# MCU.net
KiCad netlist of a schematic drawn in Altium Designer
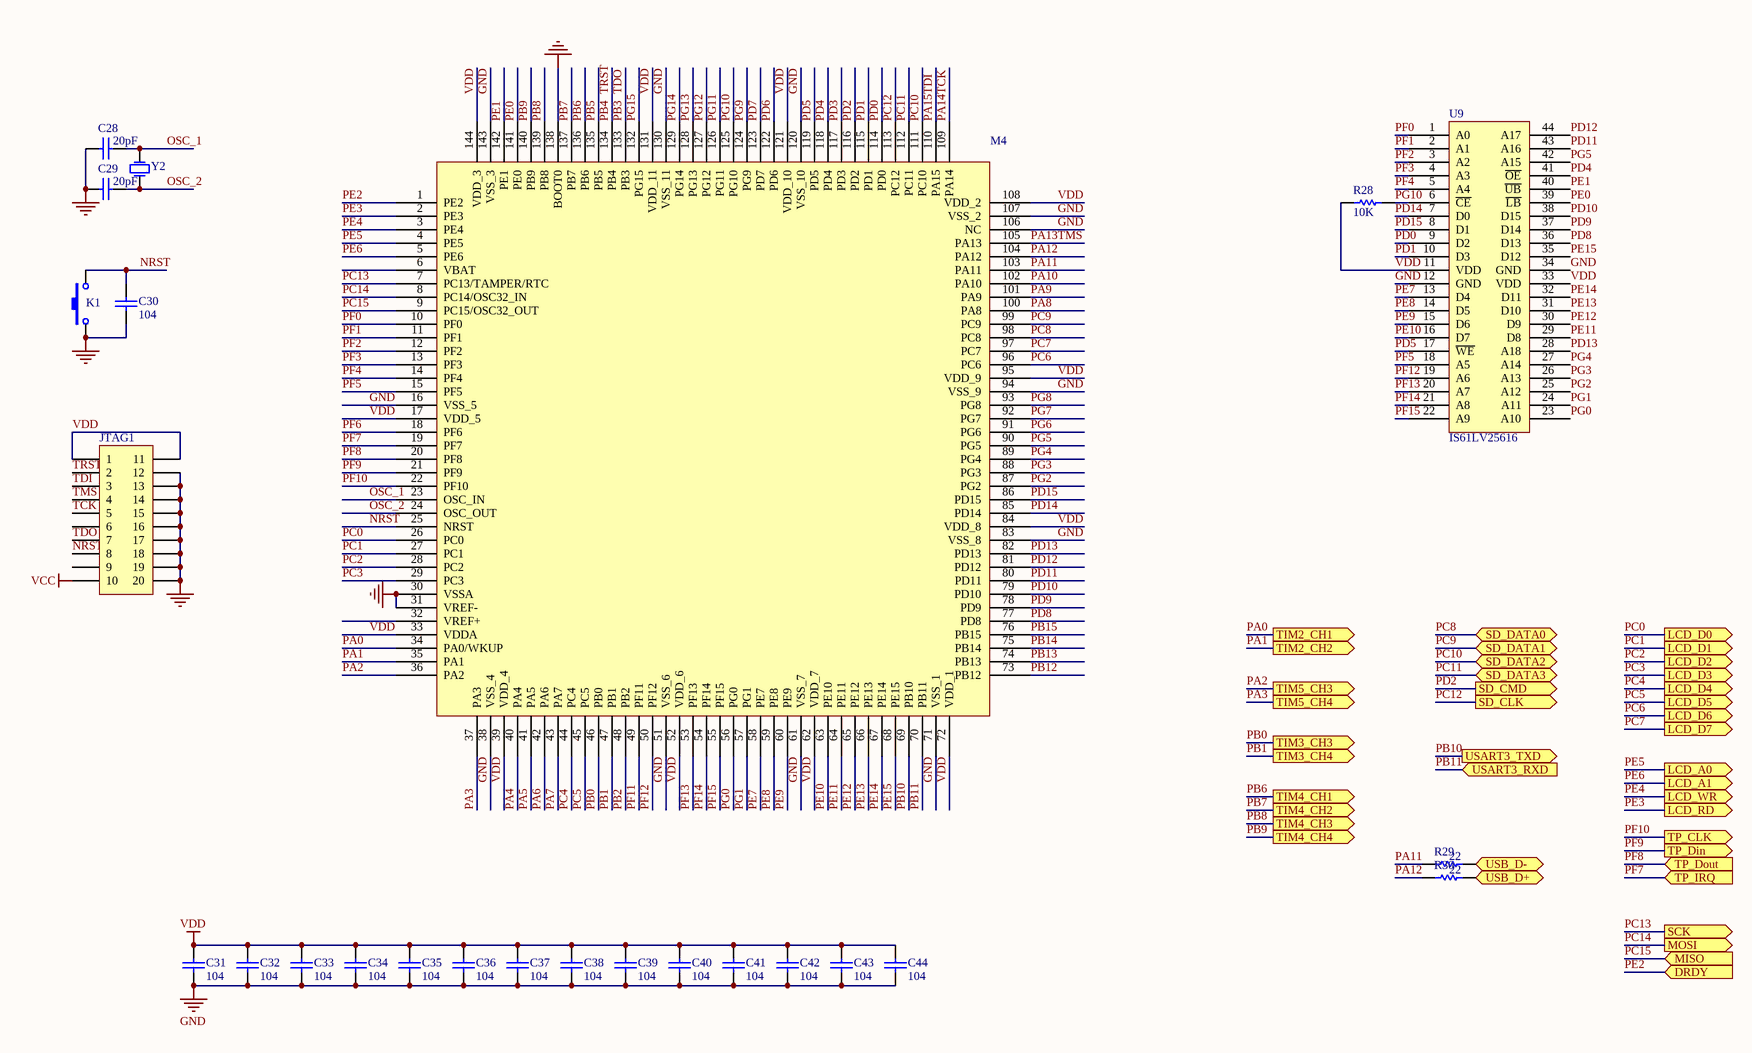
[diagram p0: MCU.SchDoc]

(export (version "E")
  (design (tool "Eeschema 10.0.6"))
  (components
    (comp (ref "C28")
      (value "20pF")
      (footprint "CR2012-0805")
      (description "Capacitor")
      (fields (field (name "Comment") "Cap") (field (name "PUBLISHER") "Altium Limited"))
      (libsource (lib "ComDev") (part "Cap"))
    )
    (comp (ref "C29")
      (value "20pF")
      (footprint "CR2012-0805")
      (description "Capacitor")
      (fields (field (name "Comment") "Cap") (field (name "PUBLISHER") "Altium Limited"))
      (libsource (lib "ComDev") (part "Cap"))
    )
    (comp (ref "C30")
      (value "104")
      (footprint "CR2012-0805")
      (description "Capacitor")
      (fields (field (name "Comment") "Cap") (field (name "PUBLISHER") "Altium Limited"))
      (libsource (lib "ComDev") (part "Cap"))
    )
    (comp (ref "C31")
      (value "104")
      (footprint "CR2012-0805")
      (description "Capacitor")
      (fields (field (name "Comment") "Cap") (field (name "PUBLISHER") "Altium Limited"))
      (libsource (lib "ComDev") (part "Cap"))
    )
    (comp (ref "C32")
      (value "104")
      (footprint "CR2012-0805")
      (description "Capacitor")
      (fields (field (name "Comment") "Cap") (field (name "PUBLISHER") "Altium Limited"))
      (libsource (lib "ComDev") (part "Cap"))
    )
    (comp (ref "C33")
      (value "104")
      (footprint "CR2012-0805")
      (description "Capacitor")
      (fields (field (name "Comment") "Cap") (field (name "PUBLISHER") "Altium Limited"))
      (libsource (lib "ComDev") (part "Cap"))
    )
    (comp (ref "C34")
      (value "104")
      (footprint "CR2012-0805")
      (description "Capacitor")
      (fields (field (name "Comment") "Cap") (field (name "PUBLISHER") "Altium Limited"))
      (libsource (lib "ComDev") (part "Cap"))
    )
    (comp (ref "C35")
      (value "104")
      (footprint "CR2012-0805")
      (description "Capacitor")
      (fields (field (name "Comment") "Cap") (field (name "PUBLISHER") "Altium Limited"))
      (libsource (lib "ComDev") (part "Cap"))
    )
    (comp (ref "C36")
      (value "104")
      (footprint "CR2012-0805")
      (description "Capacitor")
      (fields (field (name "Comment") "Cap") (field (name "PUBLISHER") "Altium Limited"))
      (libsource (lib "ComDev") (part "Cap"))
    )
    (comp (ref "C37")
      (value "104")
      (footprint "CR2012-0805")
      (description "Capacitor")
      (fields (field (name "Comment") "Cap") (field (name "PUBLISHER") "Altium Limited"))
      (libsource (lib "ComDev") (part "Cap"))
    )
    (comp (ref "C38")
      (value "104")
      (footprint "CR2012-0805")
      (description "Capacitor")
      (fields (field (name "Comment") "Cap") (field (name "PUBLISHER") "Altium Limited"))
      (libsource (lib "ComDev") (part "Cap"))
    )
    (comp (ref "C39")
      (value "104")
      (footprint "CR2012-0805")
      (description "Capacitor")
      (fields (field (name "Comment") "Cap") (field (name "PUBLISHER") "Altium Limited"))
      (libsource (lib "ComDev") (part "Cap"))
    )
    (comp (ref "C40")
      (value "104")
      (footprint "CR2012-0805")
      (description "Capacitor")
      (fields (field (name "Comment") "Cap") (field (name "PUBLISHER") "Altium Limited"))
      (libsource (lib "ComDev") (part "Cap"))
    )
    (comp (ref "C41")
      (value "104")
      (footprint "CR2012-0805")
      (description "Capacitor")
      (fields (field (name "Comment") "Cap") (field (name "PUBLISHER") "Altium Limited"))
      (libsource (lib "ComDev") (part "Cap"))
    )
    (comp (ref "C42")
      (value "104")
      (footprint "CR2012-0805")
      (description "Capacitor")
      (fields (field (name "Comment") "Cap") (field (name "PUBLISHER") "Altium Limited"))
      (libsource (lib "ComDev") (part "Cap"))
    )
    (comp (ref "C43")
      (value "104")
      (footprint "CR2012-0805")
      (description "Capacitor")
      (fields (field (name "Comment") "Cap") (field (name "PUBLISHER") "Altium Limited"))
      (libsource (lib "ComDev") (part "Cap"))
    )
    (comp (ref "C44")
      (value "104")
      (footprint "CR2012-0805")
      (description "Capacitor")
      (fields (field (name "Comment") "Cap") (field (name "PUBLISHER") "Altium Limited"))
      (libsource (lib "ComDev") (part "Cap"))
    )
    (comp (ref "JTAG1")
      (value "~")
      (footprint "HDR2X10_CEN")
      (description "Header, 10-Pin, Dual row")
      (fields (field (name "PUBLISHER") "Altium Limited"))
      (libsource (lib "Miscellaneous Connectors") (part "Header 10X2A"))
    )
    (comp (ref "K1")
      (value "SW-PB")
      (footprint "SW-PB-6.5x4.5")
      (description "Switch")
      (fields (field (name "PUBLISHER") "Altium Limited"))
      (libsource (lib "ComDev") (part "SW-PB"))
    )
    (comp (ref "M4")
      (value "STM32")
      (footprint "F-QFP20x20-G144/N")
      (libsource (lib "MCU") (part "STM32_104"))
    )
    (comp (ref "R28")
      (value "10K")
      (footprint "CR2012-0805")
      (description "Resistor")
      (fields (field (name "Comment") "Res") (field (name "PUBLISHER") "Altium Limited"))
      (libsource (lib "ComDev") (part "Res"))
    )
    (comp (ref "R29")
      (value "22")
      (footprint "CR2012-0805")
      (description "Resistor")
      (fields (field (name "Comment") "Res") (field (name "PUBLISHER") "Altium Limited"))
      (libsource (lib "ComDev") (part "Res"))
    )
    (comp (ref "R30")
      (value "22")
      (footprint "CR2012-0805")
      (description "Resistor")
      (fields (field (name "Comment") "Res") (field (name "PUBLISHER") "Altium Limited"))
      (libsource (lib "ComDev") (part "Res"))
    )
    (comp (ref "U9")
      (value "IS61LV25616")
      (footprint "SO-G44/P.8")
      (description "64K*16 SRAM")
      (libsource (lib "MCU") (part "IS61LV25616"))
    )
    (comp (ref "Y2")
      (value "XTAL")
      (footprint "XTAL")
      (description "Crystal Oscillator")
      (fields (field (name "PUBLISHER") "Altium Limited"))
      (libsource (lib "ComDev") (part "XTAL"))
    )
  )
  (nets
    (net (code "1") (name "/NRST") (class "Default")
      (node (ref "C30") (pin "2") (pinfunction "2_2") (pintype "passive"))
      (node (ref "JTAG1") (pin "8") (pinfunction "8_8") (pintype "passive"))
      (node (ref "K1") (pin "2") (pinfunction "2_2") (pintype "passive"))
      (node (ref "M4") (pin "25") (pinfunction "NRST_25") (pintype "passive"))
    )
    (net (code "2") (name "/OSC_1") (class "Default")
      (node (ref "C28") (pin "2") (pinfunction "2_2") (pintype "passive"))
      (node (ref "M4") (pin "23") (pinfunction "OSC_IN_23") (pintype "passive"))
      (node (ref "Y2") (pin "2") (pinfunction "OSC2_2") (pintype "passive"))
    )
    (net (code "3") (name "/OSC_2") (class "Default")
      (node (ref "C29") (pin "2") (pinfunction "2_2") (pintype "passive"))
      (node (ref "M4") (pin "24") (pinfunction "OSC_OUT_24") (pintype "passive"))
      (node (ref "Y2") (pin "1") (pinfunction "OSC1_1") (pintype "passive"))
    )
    (net (code "4") (name "/PA0") (class "Default")
      (node (ref "M4") (pin "34") (pinfunction "PA0/WKUP_34") (pintype "passive"))
    )
    (net (code "5") (name "/PA1") (class "Default")
      (node (ref "M4") (pin "35") (pinfunction "PA1_35") (pintype "passive"))
    )
    (net (code "6") (name "/PA2") (class "Default")
      (node (ref "M4") (pin "36") (pinfunction "PA2_36") (pintype "passive"))
    )
    (net (code "7") (name "/PA3") (class "Default")
      (node (ref "M4") (pin "37") (pinfunction "PA3_37") (pintype "passive"))
    )
    (net (code "8") (name "/PA4") (class "Default")
      (node (ref "M4") (pin "40") (pinfunction "PA4_40") (pintype "passive"))
    )
    (net (code "9") (name "/PA5") (class "Default")
      (node (ref "M4") (pin "41") (pinfunction "PA5_41") (pintype "passive"))
    )
    (net (code "10") (name "/PA6") (class "Default")
      (node (ref "M4") (pin "42") (pinfunction "PA6_42") (pintype "passive"))
    )
    (net (code "11") (name "/PA7") (class "Default")
      (node (ref "M4") (pin "43") (pinfunction "PA7_43") (pintype "passive"))
    )
    (net (code "12") (name "/PA8") (class "Default")
      (node (ref "M4") (pin "100") (pinfunction "PA8_100") (pintype "passive"))
    )
    (net (code "13") (name "/PA9") (class "Default")
      (node (ref "M4") (pin "101") (pinfunction "PA9_101") (pintype "passive"))
    )
    (net (code "14") (name "/PA10") (class "Default")
      (node (ref "M4") (pin "102") (pinfunction "PA10_102") (pintype "passive"))
    )
    (net (code "15") (name "/PA11") (class "Default")
      (node (ref "M4") (pin "103") (pinfunction "PA11_103") (pintype "passive"))
      (node (ref "R29") (pin "1") (pinfunction "1_1") (pintype "passive"))
    )
    (net (code "16") (name "/PA12") (class "Default")
      (node (ref "M4") (pin "104") (pinfunction "PA12_104") (pintype "passive"))
      (node (ref "R30") (pin "1") (pinfunction "1_1") (pintype "passive"))
    )
    (net (code "17") (name "/PA13") (class "Default")
      (node (ref "JTAG1") (pin "4") (pinfunction "4_4") (pintype "passive"))
      (node (ref "M4") (pin "105") (pinfunction "PA13_105") (pintype "passive"))
    )
    (net (code "18") (name "/PA14") (class "Default")
      (node (ref "JTAG1") (pin "5") (pinfunction "5_5") (pintype "passive"))
      (node (ref "M4") (pin "109") (pinfunction "PA14_109") (pintype "passive"))
    )
    (net (code "19") (name "/PA15") (class "Default")
      (node (ref "JTAG1") (pin "3") (pinfunction "3_3") (pintype "passive"))
      (node (ref "M4") (pin "110") (pinfunction "PA15_110") (pintype "passive"))
    )
    (net (code "20") (name "/PB0") (class "Default")
      (node (ref "M4") (pin "46") (pinfunction "PB0_46") (pintype "passive"))
    )
    (net (code "21") (name "/PB1") (class "Default")
      (node (ref "M4") (pin "47") (pinfunction "PB1_47") (pintype "passive"))
    )
    (net (code "22") (name "/PB2") (class "Default")
      (node (ref "M4") (pin "48") (pinfunction "PB2_48") (pintype "passive"))
    )
    (net (code "23") (name "/PB3") (class "Default")
      (node (ref "JTAG1") (pin "7") (pinfunction "7_7") (pintype "passive"))
      (node (ref "M4") (pin "133") (pinfunction "PB3_133") (pintype "passive"))
    )
    (net (code "24") (name "/PB4") (class "Default")
      (node (ref "JTAG1") (pin "2") (pinfunction "2_2") (pintype "passive"))
      (node (ref "M4") (pin "134") (pinfunction "PB4_134") (pintype "passive"))
    )
    (net (code "25") (name "/PB5") (class "Default")
      (node (ref "M4") (pin "135") (pinfunction "PB5_135") (pintype "passive"))
    )
    (net (code "26") (name "/PB6") (class "Default")
      (node (ref "M4") (pin "136") (pinfunction "PB6_136") (pintype "passive"))
    )
    (net (code "27") (name "/PB7") (class "Default")
      (node (ref "M4") (pin "137") (pinfunction "PB7_137") (pintype "passive"))
    )
    (net (code "28") (name "/PB8") (class "Default")
      (node (ref "M4") (pin "139") (pinfunction "PB8_139") (pintype "passive"))
    )
    (net (code "29") (name "/PB9") (class "Default")
      (node (ref "M4") (pin "140") (pinfunction "PB9_140") (pintype "passive"))
    )
    (net (code "30") (name "/PB10") (class "Default")
      (node (ref "M4") (pin "69") (pinfunction "PB10_69") (pintype "passive"))
    )
    (net (code "31") (name "/PB11") (class "Default")
      (node (ref "M4") (pin "70") (pinfunction "PB11_70") (pintype "passive"))
    )
    (net (code "32") (name "/PB12") (class "Default")
      (node (ref "M4") (pin "73") (pinfunction "PB12_73") (pintype "passive"))
    )
    (net (code "33") (name "/PB13") (class "Default")
      (node (ref "M4") (pin "74") (pinfunction "PB13_74") (pintype "passive"))
    )
    (net (code "34") (name "/PB14") (class "Default")
      (node (ref "M4") (pin "75") (pinfunction "PB14_75") (pintype "passive"))
    )
    (net (code "35") (name "/PB15") (class "Default")
      (node (ref "M4") (pin "76") (pinfunction "PB15_76") (pintype "passive"))
    )
    (net (code "36") (name "/PC0") (class "Default")
      (node (ref "M4") (pin "26") (pinfunction "PC0_26") (pintype "passive"))
    )
    (net (code "37") (name "/PC1") (class "Default")
      (node (ref "M4") (pin "27") (pinfunction "PC1_27") (pintype "passive"))
    )
    (net (code "38") (name "/PC2") (class "Default")
      (node (ref "M4") (pin "28") (pinfunction "PC2_28") (pintype "passive"))
    )
    (net (code "39") (name "/PC3") (class "Default")
      (node (ref "M4") (pin "29") (pinfunction "PC3_29") (pintype "passive"))
    )
    (net (code "40") (name "/PC4") (class "Default")
      (node (ref "M4") (pin "44") (pinfunction "PC4_44") (pintype "passive"))
    )
    (net (code "41") (name "/PC5") (class "Default")
      (node (ref "M4") (pin "45") (pinfunction "PC5_45") (pintype "passive"))
    )
    (net (code "42") (name "/PC6") (class "Default")
      (node (ref "M4") (pin "96") (pinfunction "PC6_96") (pintype "passive"))
    )
    (net (code "43") (name "/PC7") (class "Default")
      (node (ref "M4") (pin "97") (pinfunction "PC7_97") (pintype "passive"))
    )
    (net (code "44") (name "/PC8") (class "Default")
      (node (ref "M4") (pin "98") (pinfunction "PC8_98") (pintype "passive"))
    )
    (net (code "45") (name "/PC9") (class "Default")
      (node (ref "M4") (pin "99") (pinfunction "PC9_99") (pintype "passive"))
    )
    (net (code "46") (name "/PC10") (class "Default")
      (node (ref "M4") (pin "111") (pinfunction "PC10_111") (pintype "passive"))
    )
    (net (code "47") (name "/PC11") (class "Default")
      (node (ref "M4") (pin "112") (pinfunction "PC11_112") (pintype "passive"))
    )
    (net (code "48") (name "/PC12") (class "Default")
      (node (ref "M4") (pin "113") (pinfunction "PC12_113") (pintype "passive"))
    )
    (net (code "49") (name "/PC13") (class "Default")
      (node (ref "M4") (pin "7") (pinfunction "PC13/TAMPER/RTC_7") (pintype "passive"))
    )
    (net (code "50") (name "/PC14") (class "Default")
      (node (ref "M4") (pin "8") (pinfunction "PC14/OSC32_IN_8") (pintype "passive"))
    )
    (net (code "51") (name "/PC15") (class "Default")
      (node (ref "M4") (pin "9") (pinfunction "PC15/OSC32_OUT_9") (pintype "passive"))
    )
    (net (code "52") (name "/PD0") (class "Default")
      (node (ref "M4") (pin "114") (pinfunction "PD0_114") (pintype "passive"))
      (node (ref "U9") (pin "9") (pinfunction "D2_9") (pintype "passive"))
    )
    (net (code "53") (name "/PD1") (class "Default")
      (node (ref "M4") (pin "115") (pinfunction "PD1_115") (pintype "passive"))
      (node (ref "U9") (pin "10") (pinfunction "D3_10") (pintype "passive"))
    )
    (net (code "54") (name "/PD2") (class "Default")
      (node (ref "M4") (pin "116") (pinfunction "PD2_116") (pintype "passive"))
    )
    (net (code "55") (name "/PD3") (class "Default")
      (node (ref "M4") (pin "117") (pinfunction "PD3_117") (pintype "passive"))
    )
    (net (code "56") (name "/PD4") (class "Default")
      (node (ref "M4") (pin "118") (pinfunction "PD4_118") (pintype "passive"))
      (node (ref "U9") (pin "41") (pinfunction "~{OE}_41") (pintype "passive"))
    )
    (net (code "57") (name "/PD5") (class "Default")
      (node (ref "M4") (pin "119") (pinfunction "PD5_119") (pintype "passive"))
      (node (ref "U9") (pin "17") (pinfunction "~{WE}_17") (pintype "passive"))
    )
    (net (code "58") (name "/PD6") (class "Default")
      (node (ref "M4") (pin "122") (pinfunction "PD6_122") (pintype "passive"))
    )
    (net (code "59") (name "/PD7") (class "Default")
      (node (ref "M4") (pin "123") (pinfunction "PD7_123") (pintype "passive"))
    )
    (net (code "60") (name "/PD8") (class "Default")
      (node (ref "M4") (pin "77") (pinfunction "PD8_77") (pintype "passive"))
      (node (ref "U9") (pin "36") (pinfunction "D13_36") (pintype "passive"))
    )
    (net (code "61") (name "/PD9") (class "Default")
      (node (ref "M4") (pin "78") (pinfunction "PD9_78") (pintype "passive"))
      (node (ref "U9") (pin "37") (pinfunction "D14_37") (pintype "passive"))
    )
    (net (code "62") (name "/PD10") (class "Default")
      (node (ref "M4") (pin "79") (pinfunction "PD10_79") (pintype "passive"))
      (node (ref "U9") (pin "38") (pinfunction "D15_38") (pintype "passive"))
    )
    (net (code "63") (name "/PD11") (class "Default")
      (node (ref "M4") (pin "80") (pinfunction "PD11_80") (pintype "passive"))
      (node (ref "U9") (pin "43") (pinfunction "A16_43") (pintype "passive"))
    )
    (net (code "64") (name "/PD12") (class "Default")
      (node (ref "M4") (pin "81") (pinfunction "PD12_81") (pintype "passive"))
      (node (ref "U9") (pin "44") (pinfunction "A17_44") (pintype "passive"))
    )
    (net (code "65") (name "/PD13") (class "Default")
      (node (ref "M4") (pin "82") (pinfunction "PD13_82") (pintype "passive"))
      (node (ref "U9") (pin "28") (pinfunction "A18_28") (pintype "passive"))
    )
    (net (code "66") (name "/PD14") (class "Default")
      (node (ref "M4") (pin "85") (pinfunction "PD14_85") (pintype "passive"))
      (node (ref "U9") (pin "7") (pinfunction "D0_7") (pintype "passive"))
    )
    (net (code "67") (name "/PD15") (class "Default")
      (node (ref "M4") (pin "86") (pinfunction "PD15_86") (pintype "passive"))
      (node (ref "U9") (pin "8") (pinfunction "D1_8") (pintype "passive"))
    )
    (net (code "68") (name "/PE0") (class "Default")
      (node (ref "M4") (pin "141") (pinfunction "PE0_141") (pintype "passive"))
      (node (ref "U9") (pin "39") (pinfunction "~{LB}_39") (pintype "passive"))
    )
    (net (code "69") (name "/PE1") (class "Default")
      (node (ref "M4") (pin "142") (pinfunction "PE1_142") (pintype "passive"))
      (node (ref "U9") (pin "40") (pinfunction "~{UB}_40") (pintype "passive"))
    )
    (net (code "70") (name "/PE2") (class "Default")
      (node (ref "M4") (pin "1") (pinfunction "PE2_1") (pintype "passive"))
    )
    (net (code "71") (name "/PE3") (class "Default")
      (node (ref "M4") (pin "2") (pinfunction "PE3_2") (pintype "passive"))
    )
    (net (code "72") (name "/PE4") (class "Default")
      (node (ref "M4") (pin "3") (pinfunction "PE4_3") (pintype "passive"))
    )
    (net (code "73") (name "/PE5") (class "Default")
      (node (ref "M4") (pin "4") (pinfunction "PE5_4") (pintype "passive"))
    )
    (net (code "74") (name "/PE6") (class "Default")
      (node (ref "M4") (pin "5") (pinfunction "PE6_5") (pintype "passive"))
    )
    (net (code "75") (name "/PE7") (class "Default")
      (node (ref "M4") (pin "58") (pinfunction "PE7_58") (pintype "passive"))
      (node (ref "U9") (pin "13") (pinfunction "D4_13") (pintype "passive"))
    )
    (net (code "76") (name "/PE8") (class "Default")
      (node (ref "M4") (pin "59") (pinfunction "PE8_59") (pintype "passive"))
      (node (ref "U9") (pin "14") (pinfunction "D5_14") (pintype "passive"))
    )
    (net (code "77") (name "/PE9") (class "Default")
      (node (ref "M4") (pin "60") (pinfunction "PE9_60") (pintype "passive"))
      (node (ref "U9") (pin "15") (pinfunction "D6_15") (pintype "passive"))
    )
    (net (code "78") (name "/PE10") (class "Default")
      (node (ref "M4") (pin "63") (pinfunction "PE10_63") (pintype "passive"))
      (node (ref "U9") (pin "16") (pinfunction "D7_16") (pintype "passive"))
    )
    (net (code "79") (name "/PE11") (class "Default")
      (node (ref "M4") (pin "64") (pinfunction "PE11_64") (pintype "passive"))
      (node (ref "U9") (pin "29") (pinfunction "D8_29") (pintype "passive"))
    )
    (net (code "80") (name "/PE12") (class "Default")
      (node (ref "M4") (pin "65") (pinfunction "PE12_65") (pintype "passive"))
      (node (ref "U9") (pin "30") (pinfunction "D9_30") (pintype "passive"))
    )
    (net (code "81") (name "/PE13") (class "Default")
      (node (ref "M4") (pin "66") (pinfunction "PE13_66") (pintype "passive"))
      (node (ref "U9") (pin "31") (pinfunction "D10_31") (pintype "passive"))
    )
    (net (code "82") (name "/PE14") (class "Default")
      (node (ref "M4") (pin "67") (pinfunction "PE14_67") (pintype "passive"))
      (node (ref "U9") (pin "32") (pinfunction "D11_32") (pintype "passive"))
    )
    (net (code "83") (name "/PE15") (class "Default")
      (node (ref "M4") (pin "68") (pinfunction "PE15_68") (pintype "passive"))
      (node (ref "U9") (pin "35") (pinfunction "D12_35") (pintype "passive"))
    )
    (net (code "84") (name "/PF0") (class "Default")
      (node (ref "M4") (pin "10") (pinfunction "PF0_10") (pintype "passive"))
      (node (ref "U9") (pin "1") (pinfunction "A0_1") (pintype "passive"))
    )
    (net (code "85") (name "/PF1") (class "Default")
      (node (ref "M4") (pin "11") (pinfunction "PF1_11") (pintype "passive"))
      (node (ref "U9") (pin "2") (pinfunction "A1_2") (pintype "passive"))
    )
    (net (code "86") (name "/PF2") (class "Default")
      (node (ref "M4") (pin "12") (pinfunction "PF2_12") (pintype "passive"))
      (node (ref "U9") (pin "3") (pinfunction "A2_3") (pintype "passive"))
    )
    (net (code "87") (name "/PF3") (class "Default")
      (node (ref "M4") (pin "13") (pinfunction "PF3_13") (pintype "passive"))
      (node (ref "U9") (pin "4") (pinfunction "A3_4") (pintype "passive"))
    )
    (net (code "88") (name "/PF4") (class "Default")
      (node (ref "M4") (pin "14") (pinfunction "PF4_14") (pintype "passive"))
      (node (ref "U9") (pin "5") (pinfunction "A4_5") (pintype "passive"))
    )
    (net (code "89") (name "/PF5") (class "Default")
      (node (ref "M4") (pin "15") (pinfunction "PF5_15") (pintype "passive"))
      (node (ref "U9") (pin "18") (pinfunction "A5_18") (pintype "passive"))
    )
    (net (code "90") (name "/PF6") (class "Default")
      (node (ref "M4") (pin "18") (pinfunction "PF6_18") (pintype "passive"))
    )
    (net (code "91") (name "/PF7") (class "Default")
      (node (ref "M4") (pin "19") (pinfunction "PF7_19") (pintype "passive"))
    )
    (net (code "92") (name "/PF8") (class "Default")
      (node (ref "M4") (pin "20") (pinfunction "PF8_20") (pintype "passive"))
    )
    (net (code "93") (name "/PF9") (class "Default")
      (node (ref "M4") (pin "21") (pinfunction "PF9_21") (pintype "passive"))
    )
    (net (code "94") (name "/PF10") (class "Default")
      (node (ref "M4") (pin "22") (pinfunction "PF10_22") (pintype "passive"))
    )
    (net (code "95") (name "/PF11") (class "Default")
      (node (ref "M4") (pin "49") (pinfunction "PF11_49") (pintype "passive"))
    )
    (net (code "96") (name "/PF12") (class "Default")
      (node (ref "M4") (pin "50") (pinfunction "PF12_50") (pintype "passive"))
      (node (ref "U9") (pin "19") (pinfunction "A6_19") (pintype "passive"))
    )
    (net (code "97") (name "/PF13") (class "Default")
      (node (ref "M4") (pin "53") (pinfunction "PF13_53") (pintype "passive"))
      (node (ref "U9") (pin "20") (pinfunction "A7_20") (pintype "passive"))
    )
    (net (code "98") (name "/PF14") (class "Default")
      (node (ref "M4") (pin "54") (pinfunction "PF14_54") (pintype "passive"))
      (node (ref "U9") (pin "21") (pinfunction "A8_21") (pintype "passive"))
    )
    (net (code "99") (name "/PF15") (class "Default")
      (node (ref "M4") (pin "55") (pinfunction "PF15_55") (pintype "passive"))
      (node (ref "U9") (pin "22") (pinfunction "A9_22") (pintype "passive"))
    )
    (net (code "100") (name "/PG0") (class "Default")
      (node (ref "M4") (pin "56") (pinfunction "PG0_56") (pintype "passive"))
      (node (ref "U9") (pin "23") (pinfunction "A10_23") (pintype "passive"))
    )
    (net (code "101") (name "/PG1") (class "Default")
      (node (ref "M4") (pin "57") (pinfunction "PG1_57") (pintype "passive"))
      (node (ref "U9") (pin "24") (pinfunction "A11_24") (pintype "passive"))
    )
    (net (code "102") (name "/PG2") (class "Default")
      (node (ref "M4") (pin "87") (pinfunction "PG2_87") (pintype "passive"))
      (node (ref "U9") (pin "25") (pinfunction "A12_25") (pintype "passive"))
    )
    (net (code "103") (name "/PG3") (class "Default")
      (node (ref "M4") (pin "88") (pinfunction "PG3_88") (pintype "passive"))
      (node (ref "U9") (pin "26") (pinfunction "A13_26") (pintype "passive"))
    )
    (net (code "104") (name "/PG4") (class "Default")
      (node (ref "M4") (pin "89") (pinfunction "PG4_89") (pintype "passive"))
      (node (ref "U9") (pin "27") (pinfunction "A14_27") (pintype "passive"))
    )
    (net (code "105") (name "/PG5") (class "Default")
      (node (ref "M4") (pin "90") (pinfunction "PG5_90") (pintype "passive"))
      (node (ref "U9") (pin "42") (pinfunction "A15_42") (pintype "passive"))
    )
    (net (code "106") (name "/PG6") (class "Default")
      (node (ref "M4") (pin "91") (pinfunction "PG6_91") (pintype "passive"))
    )
    (net (code "107") (name "/PG7") (class "Default")
      (node (ref "M4") (pin "92") (pinfunction "PG7_92") (pintype "passive"))
    )
    (net (code "108") (name "/PG8") (class "Default")
      (node (ref "M4") (pin "93") (pinfunction "PG8_93") (pintype "passive"))
    )
    (net (code "109") (name "/PG9") (class "Default")
      (node (ref "M4") (pin "124") (pinfunction "PG9_124") (pintype "passive"))
    )
    (net (code "110") (name "/PG10") (class "Default")
      (node (ref "M4") (pin "125") (pinfunction "PG10_125") (pintype "passive"))
      (node (ref "R28") (pin "2") (pinfunction "2_2") (pintype "passive"))
      (node (ref "U9") (pin "6") (pinfunction "~{CE}_6") (pintype "passive"))
    )
    (net (code "111") (name "/PG11") (class "Default")
      (node (ref "M4") (pin "126") (pinfunction "PG11_126") (pintype "passive"))
    )
    (net (code "112") (name "/PG12") (class "Default")
      (node (ref "M4") (pin "127") (pinfunction "PG12_127") (pintype "passive"))
    )
    (net (code "113") (name "/PG13") (class "Default")
      (node (ref "M4") (pin "128") (pinfunction "PG13_128") (pintype "passive"))
    )
    (net (code "114") (name "/PG14") (class "Default")
      (node (ref "M4") (pin "129") (pinfunction "PG14_129") (pintype "passive"))
    )
    (net (code "115") (name "/PG15") (class "Default")
      (node (ref "M4") (pin "132") (pinfunction "PG15_132") (pintype "passive"))
    )
    (net (code "116") (name "/USB_D+") (class "Default")
      (node (ref "R30") (pin "2") (pinfunction "2_2") (pintype "passive"))
    )
    (net (code "117") (name "/USB_D-") (class "Default")
      (node (ref "R29") (pin "2") (pinfunction "2_2") (pintype "passive"))
    )
    (net (code "118") (name "GND") (class "Default")
      (node (ref "C28") (pin "1") (pinfunction "1_1") (pintype "passive"))
      (node (ref "C29") (pin "1") (pinfunction "1_1") (pintype "passive"))
      (node (ref "C30") (pin "1") (pinfunction "1_1") (pintype "passive"))
      (node (ref "C31") (pin "1") (pinfunction "1_1") (pintype "passive"))
      (node (ref "C32") (pin "1") (pinfunction "1_1") (pintype "passive"))
      (node (ref "C33") (pin "1") (pinfunction "1_1") (pintype "passive"))
      (node (ref "C34") (pin "1") (pinfunction "1_1") (pintype "passive"))
      (node (ref "C35") (pin "1") (pinfunction "1_1") (pintype "passive"))
      (node (ref "C36") (pin "1") (pinfunction "1_1") (pintype "passive"))
      (node (ref "C37") (pin "1") (pinfunction "1_1") (pintype "passive"))
      (node (ref "C38") (pin "1") (pinfunction "1_1") (pintype "passive"))
      (node (ref "C39") (pin "1") (pinfunction "1_1") (pintype "passive"))
      (node (ref "C40") (pin "1") (pinfunction "1_1") (pintype "passive"))
      (node (ref "C41") (pin "1") (pinfunction "1_1") (pintype "passive"))
      (node (ref "C42") (pin "1") (pinfunction "1_1") (pintype "passive"))
      (node (ref "C43") (pin "1") (pinfunction "1_1") (pintype "passive"))
      (node (ref "C44") (pin "1") (pinfunction "1_1") (pintype "passive"))
      (node (ref "JTAG1") (pin "12") (pinfunction "12_12") (pintype "passive"))
      (node (ref "JTAG1") (pin "13") (pinfunction "13_13") (pintype "passive"))
      (node (ref "JTAG1") (pin "14") (pinfunction "14_14") (pintype "passive"))
      (node (ref "JTAG1") (pin "15") (pinfunction "15_15") (pintype "passive"))
      (node (ref "JTAG1") (pin "16") (pinfunction "16_16") (pintype "passive"))
      (node (ref "JTAG1") (pin "17") (pinfunction "17_17") (pintype "passive"))
      (node (ref "JTAG1") (pin "18") (pinfunction "18_18") (pintype "passive"))
      (node (ref "JTAG1") (pin "19") (pinfunction "19_19") (pintype "passive"))
      (node (ref "JTAG1") (pin "20") (pinfunction "20_20") (pintype "passive"))
      (node (ref "K1") (pin "1") (pinfunction "1_1") (pintype "passive"))
      (node (ref "M4") (pin "106") (pinfunction "NC_106") (pintype "passive"))
      (node (ref "M4") (pin "107") (pinfunction "VSS_2_107") (pintype "passive"))
      (node (ref "M4") (pin "120") (pinfunction "VSS_10_120") (pintype "passive"))
      (node (ref "M4") (pin "130") (pinfunction "VSS_11_130") (pintype "passive"))
      (node (ref "M4") (pin "138") (pinfunction "BOOT0_138") (pintype "passive"))
      (node (ref "M4") (pin "143") (pinfunction "VSS_3_143") (pintype "passive"))
      (node (ref "M4") (pin "16") (pinfunction "VSS_5_16") (pintype "passive"))
      (node (ref "M4") (pin "30") (pinfunction "VSSA_30") (pintype "passive"))
      (node (ref "M4") (pin "31") (pinfunction "VREF-_31") (pintype "passive"))
      (node (ref "M4") (pin "38") (pinfunction "VSS_4_38") (pintype "passive"))
      (node (ref "M4") (pin "51") (pinfunction "VSS_6_51") (pintype "passive"))
      (node (ref "M4") (pin "61") (pinfunction "VSS_7_61") (pintype "passive"))
      (node (ref "M4") (pin "71") (pinfunction "VSS_1_71") (pintype "passive"))
      (node (ref "M4") (pin "83") (pinfunction "VSS_8_83") (pintype "passive"))
      (node (ref "M4") (pin "94") (pinfunction "VSS_9_94") (pintype "passive"))
      (node (ref "U9") (pin "12") (pinfunction "GND_12") (pintype "passive"))
      (node (ref "U9") (pin "34") (pinfunction "GND_34") (pintype "passive"))
    )
    (net (code "119") (name "VCC") (class "Default")
      (node (ref "JTAG1") (pin "10") (pinfunction "10_10") (pintype "passive"))
    )
    (net (code "120") (name "VDD") (class "Default")
      (node (ref "C31") (pin "2") (pinfunction "2_2") (pintype "passive"))
      (node (ref "C32") (pin "2") (pinfunction "2_2") (pintype "passive"))
      (node (ref "C33") (pin "2") (pinfunction "2_2") (pintype "passive"))
      (node (ref "C34") (pin "2") (pinfunction "2_2") (pintype "passive"))
      (node (ref "C35") (pin "2") (pinfunction "2_2") (pintype "passive"))
      (node (ref "C36") (pin "2") (pinfunction "2_2") (pintype "passive"))
      (node (ref "C37") (pin "2") (pinfunction "2_2") (pintype "passive"))
      (node (ref "C38") (pin "2") (pinfunction "2_2") (pintype "passive"))
      (node (ref "C39") (pin "2") (pinfunction "2_2") (pintype "passive"))
      (node (ref "C40") (pin "2") (pinfunction "2_2") (pintype "passive"))
      (node (ref "C41") (pin "2") (pinfunction "2_2") (pintype "passive"))
      (node (ref "C42") (pin "2") (pinfunction "2_2") (pintype "passive"))
      (node (ref "C43") (pin "2") (pinfunction "2_2") (pintype "passive"))
      (node (ref "C44") (pin "2") (pinfunction "2_2") (pintype "passive"))
      (node (ref "JTAG1") (pin "1") (pinfunction "1_1") (pintype "passive"))
      (node (ref "JTAG1") (pin "11") (pinfunction "11_11") (pintype "passive"))
      (node (ref "M4") (pin "108") (pinfunction "VDD_2_108") (pintype "passive"))
      (node (ref "M4") (pin "121") (pinfunction "VDD_10_121") (pintype "passive"))
      (node (ref "M4") (pin "131") (pinfunction "VDD_11_131") (pintype "passive"))
      (node (ref "M4") (pin "144") (pinfunction "VDD_3_144") (pintype "passive"))
      (node (ref "M4") (pin "17") (pinfunction "VDD_5_17") (pintype "passive"))
      (node (ref "M4") (pin "33") (pinfunction "VDDA_33") (pintype "passive"))
      (node (ref "M4") (pin "39") (pinfunction "VDD_4_39") (pintype "passive"))
      (node (ref "M4") (pin "52") (pinfunction "VDD_6_52") (pintype "passive"))
      (node (ref "M4") (pin "62") (pinfunction "VDD_7_62") (pintype "passive"))
      (node (ref "M4") (pin "72") (pinfunction "VDD_1_72") (pintype "passive"))
      (node (ref "M4") (pin "84") (pinfunction "VDD_8_84") (pintype "passive"))
      (node (ref "M4") (pin "95") (pinfunction "VDD_9_95") (pintype "passive"))
      (node (ref "R28") (pin "1") (pinfunction "1_1") (pintype "passive"))
      (node (ref "U9") (pin "11") (pinfunction "VDD_11") (pintype "passive"))
      (node (ref "U9") (pin "33") (pinfunction "VDD_33") (pintype "passive"))
    )
    (net (code "121") (name "unconnected-(JTAG1-Pad6)") (class "Default")
      (node (ref "JTAG1") (pin "6") (pinfunction "6_6") (pintype "passive"))
    )
    (net (code "122") (name "unconnected-(JTAG1-Pad9)") (class "Default")
      (node (ref "JTAG1") (pin "9") (pinfunction "9_9") (pintype "passive"))
    )
    (net (code "123") (name "unconnected-(M4-VBAT-Pad6)") (class "Default")
      (node (ref "M4") (pin "6") (pinfunction "VBAT_6") (pintype "passive"))
    )
    (net (code "124") (name "unconnected-(M4-VREF+-Pad32)") (class "Default")
      (node (ref "M4") (pin "32") (pinfunction "VREF+_32") (pintype "passive"))
    )
  )
)
